# 200MHz_Comb_Gen_Driver.net
KiCad netlist of a schematic drawn in Altium Designer
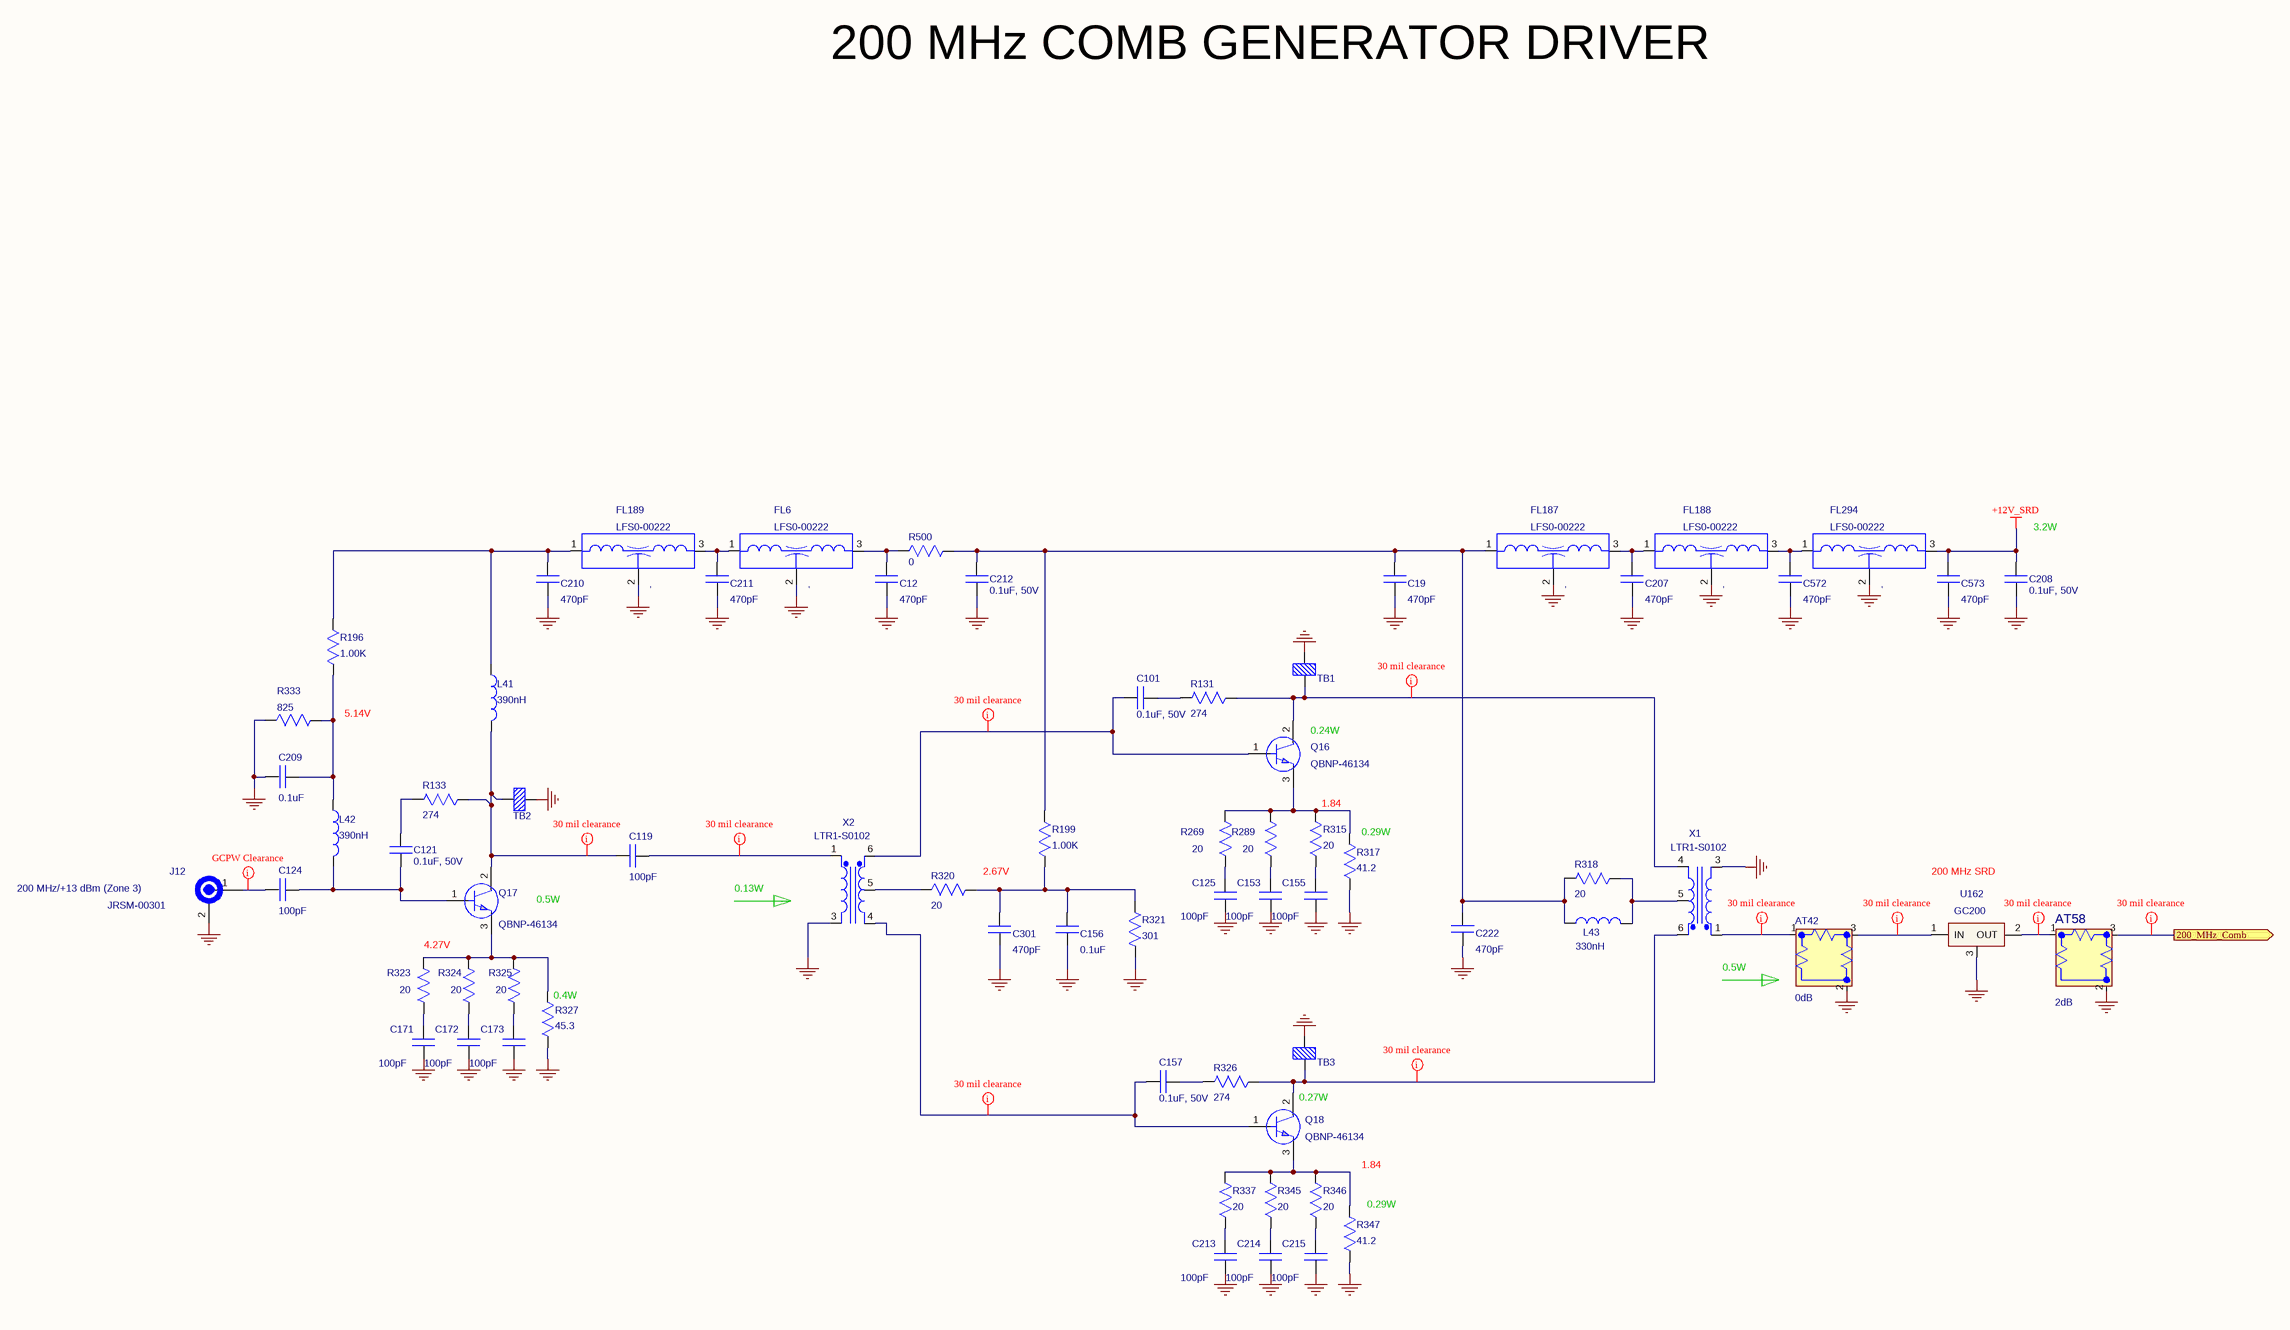
[diagram p0: 200MHz_Comb_Gen_Driver.SchDoc]

(export (version "E")
  (design (tool "Eeschema 10.0.6"))
  (components
    (comp (ref "AT42")
      (value "0dB")
      (footprint "ATTN-IMS-0805")
      (description "PAD;CHIP;0dB;+/-.3dB;.08 x .05;50 OHM;FACE DOWN")
      (fields (field (name "APPROVED") "CL"))
      (libsource (lib "Giga-tronics") (part "MPFC-A1000"))
    )
    (comp (ref "AT58")
      (value "2dB")
      (footprint "ATTN-IMS-0805")
      (description "PAD;CHIP;2dB;+/-.3dB;.08 x .05;50 OHM;FACE DOWN")
      (fields (field (name "APPROVED") "CL"))
      (libsource (lib "Giga-tronics") (part "MPFC-A1002"))
    )
    (comp (ref "C12")
      (value "470pF")
      (footprint "CAP-0402-N")
      (description "470 PF;5%;COG;>50V;CHIP;0402")
      (fields (field (name "APPROVED") "CL"))
      (libsource (lib "Giga-tronics") (part "CK40-01470"))
    )
    (comp (ref "C19")
      (value "470pF")
      (footprint "CAP-0402-N")
      (description "470 PF;5%;COG;>50V;CHIP;0402")
      (fields (field (name "APPROVED") "CL"))
      (libsource (lib "Giga-tronics") (part "CK40-01470"))
    )
    (comp (ref "C101")
      (value "0.1uF, 50V")
      (footprint "CAP-0603-N")
      (description ".1UF;5%;X7R;50V;CHIP;0603")
      (fields (field (name "APPROVED") "CL"))
      (libsource (lib "Giga-tronics") (part "CK45-14100"))
    )
    (comp (ref "C119")
      (value "100pF")
      (footprint "CAP-0402-N")
      (description "100 PF;5%;COG;>50V;CHIP;0402")
      (fields (field (name "APPROVED") "CL"))
      (libsource (lib "Giga-tronics") (part "CK40-01100"))
    )
    (comp (ref "C121")
      (value "0.1uF, 50V")
      (footprint "CAP-0603-N")
      (description ".1UF;5%;X7R;50V;CHIP;0603")
      (fields (field (name "APPROVED") "CL"))
      (libsource (lib "Giga-tronics") (part "CK45-14100"))
    )
    (comp (ref "C124")
      (value "100pF")
      (footprint "CAP-0402-N")
      (description "100 PF;5%;COG;>50V;CHIP;0402")
      (fields (field (name "APPROVED") "CL"))
      (libsource (lib "Giga-tronics") (part "CK40-01100"))
    )
    (comp (ref "C125")
      (value "100pF")
      (footprint "CAP-0402-N")
      (description "100 PF;5%;COG;>50V;CHIP;0402")
      (fields (field (name "APPROVED") "CL"))
      (libsource (lib "Giga-tronics") (part "CK40-01100"))
    )
    (comp (ref "C153")
      (value "100pF")
      (footprint "CAP-0402-N")
      (description "100 PF;5%;COG;>50V;CHIP;0402")
      (fields (field (name "APPROVED") "CL"))
      (libsource (lib "Giga-tronics") (part "CK40-01100"))
    )
    (comp (ref "C155")
      (value "100pF")
      (footprint "CAP-0402-N")
      (description "100 PF;5%;COG;>50V;CHIP;0402")
      (fields (field (name "APPROVED") "CL"))
      (libsource (lib "Giga-tronics") (part "CK40-01100"))
    )
    (comp (ref "C156")
      (value "0.1uF")
      (footprint "CAP-0402-N")
      (description ".1 UF,10%;X7R;16V,CHIP;0402")
      (fields (field (name "APPROVED") "CL"))
      (libsource (lib "Giga-tronics") (part "CK40-04100"))
    )
    (comp (ref "C157")
      (value "0.1uF, 50V")
      (footprint "CAP-0603-N")
      (description ".1UF;5%;X7R;50V;CHIP;0603")
      (fields (field (name "APPROVED") "CL"))
      (libsource (lib "Giga-tronics") (part "CK45-14100"))
    )
    (comp (ref "C171")
      (value "100pF")
      (footprint "CAP-0402-N")
      (description "100 PF;5%;COG;>50V;CHIP;0402")
      (fields (field (name "APPROVED") "CL"))
      (libsource (lib "Giga-tronics") (part "CK40-01100"))
    )
    (comp (ref "C172")
      (value "100pF")
      (footprint "CAP-0402-N")
      (description "100 PF;5%;COG;>50V;CHIP;0402")
      (fields (field (name "APPROVED") "CL"))
      (libsource (lib "Giga-tronics") (part "CK40-01100"))
    )
    (comp (ref "C173")
      (value "100pF")
      (footprint "CAP-0402-N")
      (description "100 PF;5%;COG;>50V;CHIP;0402")
      (fields (field (name "APPROVED") "CL"))
      (libsource (lib "Giga-tronics") (part "CK40-01100"))
    )
    (comp (ref "C207")
      (value "470pF")
      (footprint "CAP-0402-N")
      (description "470 PF;5%;COG;>50V;CHIP;0402")
      (fields (field (name "APPROVED") "CL"))
      (libsource (lib "Giga-tronics") (part "CK40-01470"))
    )
    (comp (ref "C208")
      (value "0.1uF, 50V")
      (footprint "CAP-0603-N")
      (description ".1UF;5%;X7R;50V;CHIP;0603")
      (fields (field (name "APPROVED") "CL"))
      (libsource (lib "Giga-tronics") (part "CK45-14100"))
    )
    (comp (ref "C209")
      (value "0.1uF")
      (footprint "CAP-0402-N")
      (description ".1 UF,10%;X7R;16V,CHIP;0402")
      (fields (field (name "APPROVED") "CL"))
      (libsource (lib "Giga-tronics") (part "CK40-04100"))
    )
    (comp (ref "C210")
      (value "470pF")
      (footprint "CAP-0402-N")
      (description "470 PF;5%;COG;>50V;CHIP;0402")
      (fields (field (name "APPROVED") "CL"))
      (libsource (lib "Giga-tronics") (part "CK40-01470"))
    )
    (comp (ref "C211")
      (value "470pF")
      (footprint "CAP-0402-N")
      (description "470 PF;5%;COG;>50V;CHIP;0402")
      (fields (field (name "APPROVED") "CL"))
      (libsource (lib "Giga-tronics") (part "CK40-01470"))
    )
    (comp (ref "C212")
      (value "0.1uF, 50V")
      (footprint "CAP-0603-N")
      (description ".1UF;5%;X7R;50V;CHIP;0603")
      (fields (field (name "APPROVED") "CL"))
      (libsource (lib "Giga-tronics") (part "CK45-14100"))
    )
    (comp (ref "C213")
      (value "100pF")
      (footprint "CAP-0402-N")
      (description "100 PF;5%;COG;>50V;CHIP;0402")
      (fields (field (name "APPROVED") "CL"))
      (libsource (lib "Giga-tronics") (part "CK40-01100"))
    )
    (comp (ref "C214")
      (value "100pF")
      (footprint "CAP-0402-N")
      (description "100 PF;5%;COG;>50V;CHIP;0402")
      (fields (field (name "APPROVED") "CL"))
      (libsource (lib "Giga-tronics") (part "CK40-01100"))
    )
    (comp (ref "C215")
      (value "100pF")
      (footprint "CAP-0402-N")
      (description "100 PF;5%;COG;>50V;CHIP;0402")
      (fields (field (name "APPROVED") "CL"))
      (libsource (lib "Giga-tronics") (part "CK40-01100"))
    )
    (comp (ref "C222")
      (value "470pF")
      (footprint "CAP-0402-N")
      (description "470 PF;5%;COG;>50V;CHIP;0402")
      (fields (field (name "APPROVED") "CL"))
      (libsource (lib "Giga-tronics") (part "CK40-01470"))
    )
    (comp (ref "C301")
      (value "470pF")
      (footprint "CAP-0402-N")
      (description "470 PF;5%;COG;>50V;CHIP;0402")
      (fields (field (name "APPROVED") "CL"))
      (libsource (lib "Giga-tronics") (part "CK40-01470"))
    )
    (comp (ref "C572")
      (value "470pF")
      (footprint "CAP-0402-N")
      (description "470 PF;5%;COG;>50V;CHIP;0402")
      (fields (field (name "APPROVED") "CL"))
      (libsource (lib "Giga-tronics") (part "CK40-01470"))
    )
    (comp (ref "C573")
      (value "470pF")
      (footprint "CAP-0402-N")
      (description "470 PF;5%;COG;>50V;CHIP;0402")
      (fields (field (name "APPROVED") "CL"))
      (libsource (lib "Giga-tronics") (part "CK40-01470"))
    )
    (comp (ref "FL6")
      (value "Filter EMI 2200PF,1206")
      (footprint "FIL-NFE31P-1206-4P")
      (fields (field (name "G_PN") "LFS0-00222") (field (name "APPROVED") "CL"))
      (libsource (lib "Giga-tronics") (part "LFS0-00222"))
    )
    (comp (ref "FL187")
      (value "Filter EMI 2200PF,1206")
      (footprint "FIL-NFE31P-1206-4P")
      (fields (field (name "G_PN") "LFS0-00222") (field (name "APPROVED") "CL"))
      (libsource (lib "Giga-tronics") (part "LFS0-00222"))
    )
    (comp (ref "FL188")
      (value "Filter EMI 2200PF,1206")
      (footprint "FIL-NFE31P-1206-4P")
      (fields (field (name "G_PN") "LFS0-00222") (field (name "APPROVED") "CL"))
      (libsource (lib "Giga-tronics") (part "LFS0-00222"))
    )
    (comp (ref "FL189")
      (value "Filter EMI 2200PF,1206")
      (footprint "FIL-NFE31P-1206-4P")
      (fields (field (name "G_PN") "LFS0-00222") (field (name "APPROVED") "CL"))
      (libsource (lib "Giga-tronics") (part "LFS0-00222"))
    )
    (comp (ref "FL294")
      (value "Filter EMI 2200PF,1206")
      (footprint "FIL-NFE31P-1206-4P")
      (fields (field (name "G_PN") "LFS0-00222") (field (name "APPROVED") "CL"))
      (libsource (lib "Giga-tronics") (part "LFS0-00222"))
    )
    (comp (ref "J12")
      (value "200 MHz/+13 dBm (Zone 3)")
      (footprint "CONN-3211-60035_plane_cutout")
      (description "SMPM;SB EDGE LAUNCH;MALE;1 PORT")
      (fields (field (name "G_PN") "JRSM-00301") (field (name "APPROVED") "CL"))
      (libsource (lib "Giga-tronics") (part "JRSM-00301"))
    )
    (comp (ref "L41")
      (value "390nH")
      (footprint "IND-0603CS")
      (description "INDUCTOR;390NH;5%;.78GHZ SRF;25Q;4.35 DCR;100MA;WIREWOUND;0603")
      (fields (field (name "APPROVED") "CL"))
      (libsource (lib "Giga-tronics") (part "LSA3-04390"))
    )
    (comp (ref "L42")
      (value "390nH")
      (footprint "IND-0603CS")
      (description "INDUCTOR;390NH;5%;.78GHZ SRF;25Q;4.35 DCR;100MA;WIREWOUND;0603")
      (fields (field (name "APPROVED") "CL"))
      (libsource (lib "Giga-tronics") (part "LSA3-04390"))
    )
    (comp (ref "L43")
      (value "330nH")
      (footprint "IND-1008CS")
      (description "INDUCTOR;.33 UH;5%;570 MHZ SRF;45Q @100MHZ;1.05 DCR;450MA;WIREWOUND;1008")
      (fields (field (name "APPROVED") "CL"))
      (libsource (lib "Giga-tronics") (part "LSA1-04330"))
    )
    (comp (ref "Q16")
      (value ".")
      (footprint "SOT89-3N")
      (description "27.5 dBm @1GHz;5.5 GHz fT;15V MAX;250 mA MAX;SOT-89")
      (fields (field (name "G_PN") "QBNP-46134") (field (name "APPROVED") "NM"))
      (libsource (lib "Giga-tronics") (part "QBNP-46134"))
    )
    (comp (ref "Q17")
      (value ".")
      (footprint "SOT89-3N")
      (description "27.5 dBm @1GHz;5.5 GHz fT;15V MAX;250 mA MAX;SOT-89")
      (fields (field (name "G_PN") "QBNP-46134") (field (name "APPROVED") "NM"))
      (libsource (lib "Giga-tronics") (part "QBNP-46134"))
    )
    (comp (ref "Q18")
      (value ".")
      (footprint "SOT89-3N")
      (description "27.5 dBm @1GHz;5.5 GHz fT;15V MAX;250 mA MAX;SOT-89")
      (fields (field (name "G_PN") "QBNP-46134") (field (name "APPROVED") "NM"))
      (libsource (lib "Giga-tronics") (part "QBNP-46134"))
    )
    (comp (ref "R131")
      (value "274")
      (footprint "RES-0402-N")
      (description "274 OHMS; 1%; .1W; 100PPM; FILM; CHIP; 0402")
      (fields (field (name "APPROVED") "CL"))
      (libsource (lib "Giga-tronics") (part "RK35-02740"))
    )
    (comp (ref "R133")
      (value "274")
      (footprint "RES-0402-N")
      (description "274 OHMS; 1%; .1W; 100PPM; FILM; CHIP; 0402")
      (fields (field (name "APPROVED") "CL"))
      (libsource (lib "Giga-tronics") (part "RK35-02740"))
    )
    (comp (ref "R196")
      (value "1.00K")
      (footprint "RES-0402-N")
      (description "1.0K OHMS;.06W;1%;200PPM;FILM;CHIP;0402")
      (fields (field (name "APPROVED") "CL"))
      (libsource (lib "Giga-tronics") (part "RK35-11000"))
    )
    (comp (ref "R199")
      (value "1.00K")
      (footprint "RES-0402-N")
      (description "1.0K OHMS;.06W;1%;200PPM;FILM;CHIP;0402")
      (fields (field (name "APPROVED") "CL"))
      (libsource (lib "Giga-tronics") (part "RK35-11000"))
    )
    (comp (ref "R269")
      (value "20")
      (footprint "RES-0402-N")
      (description "20 OHMS;.06W;1%;200PPM;FILM;CHIP;0402")
      (fields (field (name "APPROVED") "CL"))
      (libsource (lib "Giga-tronics") (part "RK35-00200"))
    )
    (comp (ref "R289")
      (value "20")
      (footprint "RES-0402-N")
      (description "20 OHMS;.06W;1%;200PPM;FILM;CHIP;0402")
      (fields (field (name "APPROVED") "CL"))
      (libsource (lib "Giga-tronics") (part "RK35-00200"))
    )
    (comp (ref "R315")
      (value "20")
      (footprint "RES-0402-N")
      (description "20 OHMS;.06W;1%;200PPM;FILM;CHIP;0402")
      (fields (field (name "APPROVED") "CL"))
      (libsource (lib "Giga-tronics") (part "RK35-00200"))
    )
    (comp (ref "R317")
      (value "41.2")
      (footprint "RES-2010-N")
      (description "41.2 OHMS;.75W;1%;100PPM;THICK FILM;CHIP;2010;RoHS")
      (fields (field (name "APPROVED") "CL"))
      (libsource (lib "Giga-tronics") (part "RK65-00412"))
    )
    (comp (ref "R318")
      (value "20")
      (footprint "RES-0402-N")
      (description "20 OHMS;.06W;1%;200PPM;FILM;CHIP;0402")
      (fields (field (name "APPROVED") "CL"))
      (libsource (lib "Giga-tronics") (part "RK35-00200"))
    )
    (comp (ref "R320")
      (value "20")
      (footprint "RES-0402-N")
      (description "20 OHMS;.06W;1%;200PPM;FILM;CHIP;0402")
      (fields (field (name "APPROVED") "CL"))
      (libsource (lib "Giga-tronics") (part "RK35-00200"))
    )
    (comp (ref "R321")
      (value "301")
      (footprint "RES-0402-N")
      (description "301 OHMS; 1%; .1W; 100PPM; FILM; CHIP; 0402")
      (fields (field (name "APPROVED") "CL"))
      (libsource (lib "Giga-tronics") (part "RK35-03010"))
    )
    (comp (ref "R323")
      (value "20")
      (footprint "RES-0402-N")
      (description "20 OHMS;.06W;1%;200PPM;FILM;CHIP;0402")
      (fields (field (name "APPROVED") "CL"))
      (libsource (lib "Giga-tronics") (part "RK35-00200"))
    )
    (comp (ref "R324")
      (value "20")
      (footprint "RES-0402-N")
      (description "20 OHMS;.06W;1%;200PPM;FILM;CHIP;0402")
      (fields (field (name "APPROVED") "CL"))
      (libsource (lib "Giga-tronics") (part "RK35-00200"))
    )
    (comp (ref "R325")
      (value "20")
      (footprint "RES-0402-N")
      (description "20 OHMS;.06W;1%;200PPM;FILM;CHIP;0402")
      (fields (field (name "APPROVED") "CL"))
      (libsource (lib "Giga-tronics") (part "RK35-00200"))
    )
    (comp (ref "R326")
      (value "274")
      (footprint "RES-0402-N")
      (description "274 OHMS; 1%; .1W; 100PPM; FILM; CHIP; 0402")
      (fields (field (name "APPROVED") "CL"))
      (libsource (lib "Giga-tronics") (part "RK35-02740"))
    )
    (comp (ref "R327")
      (value "45.3")
      (footprint "RES-2010-N")
      (description "45.3 OHMS;0.75W;1%;100PPM;THICK FILM;CHIP;2010;RoHS")
      (fields (field (name "APPROVED") "CL"))
      (libsource (lib "Giga-tronics") (part "RK65-00453"))
    )
    (comp (ref "R333")
      (value "825")
      (footprint "RES-0402-N")
      (description "825 OHMS; 1%; .1W; 100PPM; FILM; CHIP; 0402")
      (fields (field (name "APPROVED") "CL"))
      (libsource (lib "Giga-tronics") (part "RK35-08250"))
    )
    (comp (ref "R337")
      (value "20")
      (footprint "RES-0402-N")
      (description "20 OHMS;.06W;1%;200PPM;FILM;CHIP;0402")
      (fields (field (name "APPROVED") "CL"))
      (libsource (lib "Giga-tronics") (part "RK35-00200"))
    )
    (comp (ref "R345")
      (value "20")
      (footprint "RES-0402-N")
      (description "20 OHMS;.06W;1%;200PPM;FILM;CHIP;0402")
      (fields (field (name "APPROVED") "CL"))
      (libsource (lib "Giga-tronics") (part "RK35-00200"))
    )
    (comp (ref "R346")
      (value "20")
      (footprint "RES-0402-N")
      (description "20 OHMS;.06W;1%;200PPM;FILM;CHIP;0402")
      (fields (field (name "APPROVED") "CL"))
      (libsource (lib "Giga-tronics") (part "RK35-00200"))
    )
    (comp (ref "R347")
      (value "41.2")
      (footprint "RES-2010-N")
      (description "41.2 OHMS;.75W;1%;100PPM;THICK FILM;CHIP;2010;RoHS")
      (fields (field (name "APPROVED") "CL"))
      (libsource (lib "Giga-tronics") (part "RK65-00412"))
    )
    (comp (ref "R500")
      (value "0")
      (footprint "RES-0402-N")
      (description "JUMPER;0 OHMS;SMT;0402")
      (fields (field (name "APPROVED") "CL"))
      (libsource (lib "Giga-tronics") (part "RK35-00000"))
    )
    (comp (ref "TB1")
      (value "THERMAL BRIDGE, AlN, 1010")
      (footprint "TB-1010-N")
      (fields (field (name "APPROVED") "CL"))
      (libsource (lib "Giga-tronics") (part "BK51-00000"))
    )
    (comp (ref "TB2")
      (value "THERMAL BRIDGE, AlN, 1010")
      (footprint "TB-1010-N")
      (fields (field (name "APPROVED") "CL"))
      (libsource (lib "Giga-tronics") (part "BK51-00000"))
    )
    (comp (ref "TB3")
      (value "THERMAL BRIDGE, AlN, 1010")
      (footprint "TB-1010-N")
      (fields (field (name "APPROVED") "CL"))
      (libsource (lib "Giga-tronics") (part "BK51-00000"))
    )
    (comp (ref "U162")
      (value "DIODE;SRD;COAXIAL;200MHz COM GEN")
      (footprint "checked_Hydra A2 Ref:DIO-GC-OUTLINE-L")
      (fields (field (name "M_PN") "GC200") (field (name "APPROVED") "NM"))
      (libsource (lib "Giga-tronics") (part "DIA0-00200"))
    )
    (comp (ref "X1")
      (value "XFORMER;1:2Z CT;8-600 MHZ;1W;30MA;CD542 CASE")
      (footprint "XFMR-CD542")
      (fields (field (name "G_PN") "LTR1-S0102") (field (name "APPROVED") "NM"))
      (libsource (lib "Giga-tronics") (part "LTR1-S0102"))
    )
    (comp (ref "X2")
      (value "XFORMER;1:2Z CT;8-600 MHZ;1W;30MA;CD542 CASE")
      (footprint "XFMR-CD542")
      (fields (field (name "G_PN") "LTR1-S0102") (field (name "APPROVED") "NM"))
      (libsource (lib "Giga-tronics") (part "LTR1-S0102"))
    )
  )
  (nets
    (net (code "1") (name "+12V_SRD") (class "Default")
      (node (ref "C208") (pin "1") (pintype "passive"))
      (node (ref "C573") (pin "1") (pintype "passive"))
      (node (ref "FL294") (pin "3") (pinfunction "OUT_3") (pintype "passive"))
    )
    (net (code "2") (name "/200_MHz_Comb") (class "Default")
      (node (ref "AT58") (pin "3") (pinfunction "IN/OUT_3") (pintype "passive"))
    )
    (net (code "3") (name "GND") (class "Default")
      (node (ref "AT42") (pin "2") (pinfunction "GND_2") (pintype "power_in"))
      (node (ref "AT58") (pin "2") (pinfunction "GND_2") (pintype "power_in"))
      (node (ref "C12") (pin "2") (pintype "passive"))
      (node (ref "C125") (pin "1") (pintype "passive"))
      (node (ref "C153") (pin "1") (pintype "passive"))
      (node (ref "C155") (pin "1") (pintype "passive"))
      (node (ref "C156") (pin "1") (pintype "passive"))
      (node (ref "C171") (pin "1") (pintype "passive"))
      (node (ref "C172") (pin "1") (pintype "passive"))
      (node (ref "C173") (pin "1") (pintype "passive"))
      (node (ref "C19") (pin "2") (pintype "passive"))
      (node (ref "C207") (pin "2") (pintype "passive"))
      (node (ref "C208") (pin "2") (pintype "passive"))
      (node (ref "C209") (pin "2") (pintype "passive"))
      (node (ref "C210") (pin "2") (pintype "passive"))
      (node (ref "C211") (pin "2") (pintype "passive"))
      (node (ref "C212") (pin "2") (pintype "passive"))
      (node (ref "C213") (pin "1") (pintype "passive"))
      (node (ref "C214") (pin "1") (pintype "passive"))
      (node (ref "C215") (pin "1") (pintype "passive"))
      (node (ref "C222") (pin "2") (pintype "passive"))
      (node (ref "C301") (pin "1") (pintype "passive"))
      (node (ref "C572") (pin "2") (pintype "passive"))
      (node (ref "C573") (pin "2") (pintype "passive"))
      (node (ref "FL187") (pin "2") (pinfunction "GND_2") (pintype "passive"))
      (node (ref "FL188") (pin "2") (pinfunction "GND_2") (pintype "passive"))
      (node (ref "FL189") (pin "2") (pinfunction "GND_2") (pintype "passive"))
      (node (ref "FL294") (pin "2") (pinfunction "GND_2") (pintype "passive"))
      (node (ref "FL6") (pin "2") (pinfunction "GND_2") (pintype "passive"))
      (node (ref "J12") (pin "2") (pinfunction "GND_2") (pintype "passive"))
      (node (ref "R317") (pin "2") (pintype "passive"))
      (node (ref "R321") (pin "1") (pintype "passive"))
      (node (ref "R327") (pin "2") (pintype "passive"))
      (node (ref "R333") (pin "2") (pintype "passive"))
      (node (ref "R347") (pin "2") (pintype "passive"))
      (node (ref "TB1") (pin "2") (pintype "passive"))
      (node (ref "TB2") (pin "2") (pintype "passive"))
      (node (ref "TB3") (pin "2") (pintype "passive"))
      (node (ref "U162") (pin "3") (pinfunction "GND_3") (pintype "passive"))
      (node (ref "X1") (pin "3") (pinfunction "Pri-_3") (pintype "passive"))
      (node (ref "X2") (pin "3") (pinfunction "Pri-_3") (pintype "passive"))
    )
    (net (code "4") (name "Net-(C101-Pad2)") (class "Default")
      (node (ref "C101") (pin "2") (pintype "passive"))
      (node (ref "R131") (pin "1") (pintype "passive"))
    )
    (net (code "5") (name "Net-(C121-Pad1)") (class "Default")
      (node (ref "C121") (pin "1") (pintype "passive"))
      (node (ref "R133") (pin "1") (pintype "passive"))
    )
    (net (code "6") (name "Net-(C124-Pad2)") (class "Default")
      (node (ref "C124") (pin "2") (pintype "passive"))
      (node (ref "J12") (pin "1") (pinfunction "1_1") (pintype "passive"))
    )
    (net (code "7") (name "Net-(C125-Pad2)") (class "Default")
      (node (ref "C125") (pin "2") (pintype "passive"))
      (node (ref "R269") (pin "2") (pintype "passive"))
    )
    (net (code "8") (name "Net-(C153-Pad2)") (class "Default")
      (node (ref "C153") (pin "2") (pintype "passive"))
      (node (ref "R289") (pin "2") (pintype "passive"))
    )
    (net (code "9") (name "Net-(C155-Pad2)") (class "Default")
      (node (ref "C155") (pin "2") (pintype "passive"))
      (node (ref "R315") (pin "2") (pintype "passive"))
    )
    (net (code "10") (name "Net-(C156-Pad2)") (class "Default")
      (node (ref "C156") (pin "2") (pintype "passive"))
      (node (ref "C301") (pin "2") (pintype "passive"))
      (node (ref "R199") (pin "1") (pintype "passive"))
      (node (ref "R320") (pin "1") (pintype "passive"))
      (node (ref "R321") (pin "2") (pintype "passive"))
    )
    (net (code "11") (name "Net-(C157-Pad2)") (class "Default")
      (node (ref "C157") (pin "2") (pintype "passive"))
      (node (ref "R326") (pin "1") (pintype "passive"))
    )
    (net (code "12") (name "Net-(C171-Pad2)") (class "Default")
      (node (ref "C171") (pin "2") (pintype "passive"))
      (node (ref "R323") (pin "2") (pintype "passive"))
    )
    (net (code "13") (name "Net-(C172-Pad2)") (class "Default")
      (node (ref "C172") (pin "2") (pintype "passive"))
      (node (ref "R324") (pin "2") (pintype "passive"))
    )
    (net (code "14") (name "Net-(C173-Pad2)") (class "Default")
      (node (ref "C173") (pin "2") (pintype "passive"))
      (node (ref "R325") (pin "2") (pintype "passive"))
    )
    (net (code "15") (name "Net-(C209-Pad1)") (class "Default")
      (node (ref "C209") (pin "1") (pintype "passive"))
      (node (ref "L42") (pin "1") (pinfunction "1_1") (pintype "passive"))
      (node (ref "R196") (pin "1") (pintype "passive"))
      (node (ref "R333") (pin "1") (pintype "passive"))
    )
    (net (code "16") (name "Net-(C213-Pad2)") (class "Default")
      (node (ref "C213") (pin "2") (pintype "passive"))
      (node (ref "R337") (pin "2") (pintype "passive"))
    )
    (net (code "17") (name "Net-(C214-Pad2)") (class "Default")
      (node (ref "C214") (pin "2") (pintype "passive"))
      (node (ref "R345") (pin "2") (pintype "passive"))
    )
    (net (code "18") (name "Net-(C215-Pad2)") (class "Default")
      (node (ref "C215") (pin "2") (pintype "passive"))
      (node (ref "R346") (pin "2") (pintype "passive"))
    )
    (net (code "19") (name "Net-(FL6-OUT)") (class "Default")
      (node (ref "C12") (pin "1") (pintype "passive"))
      (node (ref "FL6") (pin "3") (pinfunction "OUT_3") (pintype "passive"))
      (node (ref "R500") (pin "2") (pintype "passive"))
    )
    (net (code "20") (name "Net-(FL187-IN)") (class "Default")
      (node (ref "C19") (pin "1") (pintype "passive"))
      (node (ref "C212") (pin "1") (pintype "passive"))
      (node (ref "C222") (pin "1") (pintype "passive"))
      (node (ref "FL187") (pin "1") (pinfunction "IN_1") (pintype "passive"))
      (node (ref "L43") (pin "1") (pinfunction "1_1") (pintype "passive"))
      (node (ref "R199") (pin "2") (pintype "passive"))
      (node (ref "R318") (pin "1") (pintype "passive"))
      (node (ref "R500") (pin "1") (pintype "passive"))
    )
    (net (code "21") (name "Net-(FL187-OUT)") (class "Default")
      (node (ref "C207") (pin "1") (pintype "passive"))
      (node (ref "FL187") (pin "3") (pinfunction "OUT_3") (pintype "passive"))
      (node (ref "FL188") (pin "1") (pinfunction "IN_1") (pintype "passive"))
    )
    (net (code "22") (name "Net-(FL188-OUT)") (class "Default")
      (node (ref "C572") (pin "1") (pintype "passive"))
      (node (ref "FL188") (pin "3") (pinfunction "OUT_3") (pintype "passive"))
      (node (ref "FL294") (pin "1") (pinfunction "IN_1") (pintype "passive"))
    )
    (net (code "23") (name "Net-(FL189-IN)") (class "Default")
      (node (ref "C210") (pin "1") (pintype "passive"))
      (node (ref "FL189") (pin "1") (pinfunction "IN_1") (pintype "passive"))
      (node (ref "L41") (pin "1") (pinfunction "1_1") (pintype "passive"))
      (node (ref "R196") (pin "2") (pintype "passive"))
    )
    (net (code "24") (name "Net-(FL189-OUT)") (class "Default")
      (node (ref "C211") (pin "1") (pintype "passive"))
      (node (ref "FL189") (pin "3") (pinfunction "OUT_3") (pintype "passive"))
      (node (ref "FL6") (pin "1") (pinfunction "IN_1") (pintype "passive"))
    )
    (net (code "25") (name "Net-(Q16-BASE)") (class "Default")
      (node (ref "C101") (pin "1") (pintype "passive"))
      (node (ref "Q16") (pin "1") (pinfunction "BASE_1") (pintype "passive"))
      (node (ref "X2") (pin "6") (pinfunction "Sec+_6") (pintype "passive"))
    )
    (net (code "26") (name "Net-(Q16-COLLECTOR)") (class "Default")
      (node (ref "Q16") (pin "2") (pinfunction "COLLECTOR_2") (pintype "passive"))
      (node (ref "R131") (pin "2") (pintype "passive"))
      (node (ref "TB1") (pin "1") (pintype "passive"))
      (node (ref "X1") (pin "4") (pinfunction "Sec-_4") (pintype "passive"))
    )
    (net (code "27") (name "Net-(Q16-EMITTER)") (class "Default")
      (node (ref "Q16") (pin "3") (pinfunction "EMITTER_3") (pintype "passive"))
      (node (ref "R269") (pin "1") (pintype "passive"))
      (node (ref "R289") (pin "1") (pintype "passive"))
      (node (ref "R315") (pin "1") (pintype "passive"))
      (node (ref "R317") (pin "1") (pintype "passive"))
    )
    (net (code "28") (name "Net-(Q17-BASE)") (class "Default")
      (node (ref "C121") (pin "2") (pintype "passive"))
      (node (ref "C124") (pin "1") (pintype "passive"))
      (node (ref "L42") (pin "2") (pinfunction "2_2") (pintype "passive"))
      (node (ref "Q17") (pin "1") (pinfunction "BASE_1") (pintype "passive"))
    )
    (net (code "29") (name "Net-(Q17-COLLECTOR)") (class "Default")
      (node (ref "C119") (pin "2") (pintype "passive"))
      (node (ref "L41") (pin "2") (pinfunction "2_2") (pintype "passive"))
      (node (ref "Q17") (pin "2") (pinfunction "COLLECTOR_2") (pintype "passive"))
      (node (ref "R133") (pin "2") (pintype "passive"))
      (node (ref "TB2") (pin "1") (pintype "passive"))
    )
    (net (code "30") (name "Net-(Q17-EMITTER)") (class "Default")
      (node (ref "Q17") (pin "3") (pinfunction "EMITTER_3") (pintype "passive"))
      (node (ref "R323") (pin "1") (pintype "passive"))
      (node (ref "R324") (pin "1") (pintype "passive"))
      (node (ref "R325") (pin "1") (pintype "passive"))
      (node (ref "R327") (pin "1") (pintype "passive"))
    )
    (net (code "31") (name "Net-(Q18-BASE)") (class "Default")
      (node (ref "C157") (pin "1") (pintype "passive"))
      (node (ref "Q18") (pin "1") (pinfunction "BASE_1") (pintype "passive"))
      (node (ref "X2") (pin "4") (pinfunction "Sec-_4") (pintype "passive"))
    )
    (net (code "32") (name "Net-(Q18-COLLECTOR)") (class "Default")
      (node (ref "Q18") (pin "2") (pinfunction "COLLECTOR_2") (pintype "passive"))
      (node (ref "R326") (pin "2") (pintype "passive"))
      (node (ref "TB3") (pin "1") (pintype "passive"))
      (node (ref "X1") (pin "6") (pinfunction "Sec+_6") (pintype "passive"))
    )
    (net (code "33") (name "Net-(Q18-EMITTER)") (class "Default")
      (node (ref "Q18") (pin "3") (pinfunction "EMITTER_3") (pintype "passive"))
      (node (ref "R337") (pin "1") (pintype "passive"))
      (node (ref "R345") (pin "1") (pintype "passive"))
      (node (ref "R346") (pin "1") (pintype "passive"))
      (node (ref "R347") (pin "1") (pintype "passive"))
    )
    (net (code "34") (name "Net-(U162-IN)") (class "Default")
      (node (ref "AT42") (pin "3") (pinfunction "IN/OUT_3") (pintype "passive"))
      (node (ref "U162") (pin "1") (pinfunction "IN_1") (pintype "passive"))
    )
    (net (code "35") (name "Net-(U162-OUT)") (class "Default")
      (node (ref "AT58") (pin "1") (pinfunction "IN/OUT_1") (pintype "passive"))
      (node (ref "U162") (pin "2") (pinfunction "OUT_2") (pintype "passive"))
    )
    (net (code "36") (name "Net-(X1-Pri+)") (class "Default")
      (node (ref "AT42") (pin "1") (pinfunction "IN/OUT_1") (pintype "passive"))
      (node (ref "X1") (pin "1") (pinfunction "Pri+_1") (pintype "passive"))
    )
    (net (code "37") (name "Net-(X1-SecCT)") (class "Default")
      (node (ref "L43") (pin "2") (pinfunction "2_2") (pintype "passive"))
      (node (ref "R318") (pin "2") (pintype "passive"))
      (node (ref "X1") (pin "5") (pinfunction "SecCT_5") (pintype "passive"))
    )
    (net (code "38") (name "Net-(X2-Pri+)") (class "Default")
      (node (ref "C119") (pin "1") (pintype "passive"))
      (node (ref "X2") (pin "1") (pinfunction "Pri+_1") (pintype "passive"))
    )
    (net (code "39") (name "Net-(X2-SecCT)") (class "Default")
      (node (ref "R320") (pin "2") (pintype "passive"))
      (node (ref "X2") (pin "5") (pinfunction "SecCT_5") (pintype "passive"))
    )
  )
)
